# mcu.net
KiCad netlist of a schematic drawn in Altium Designer
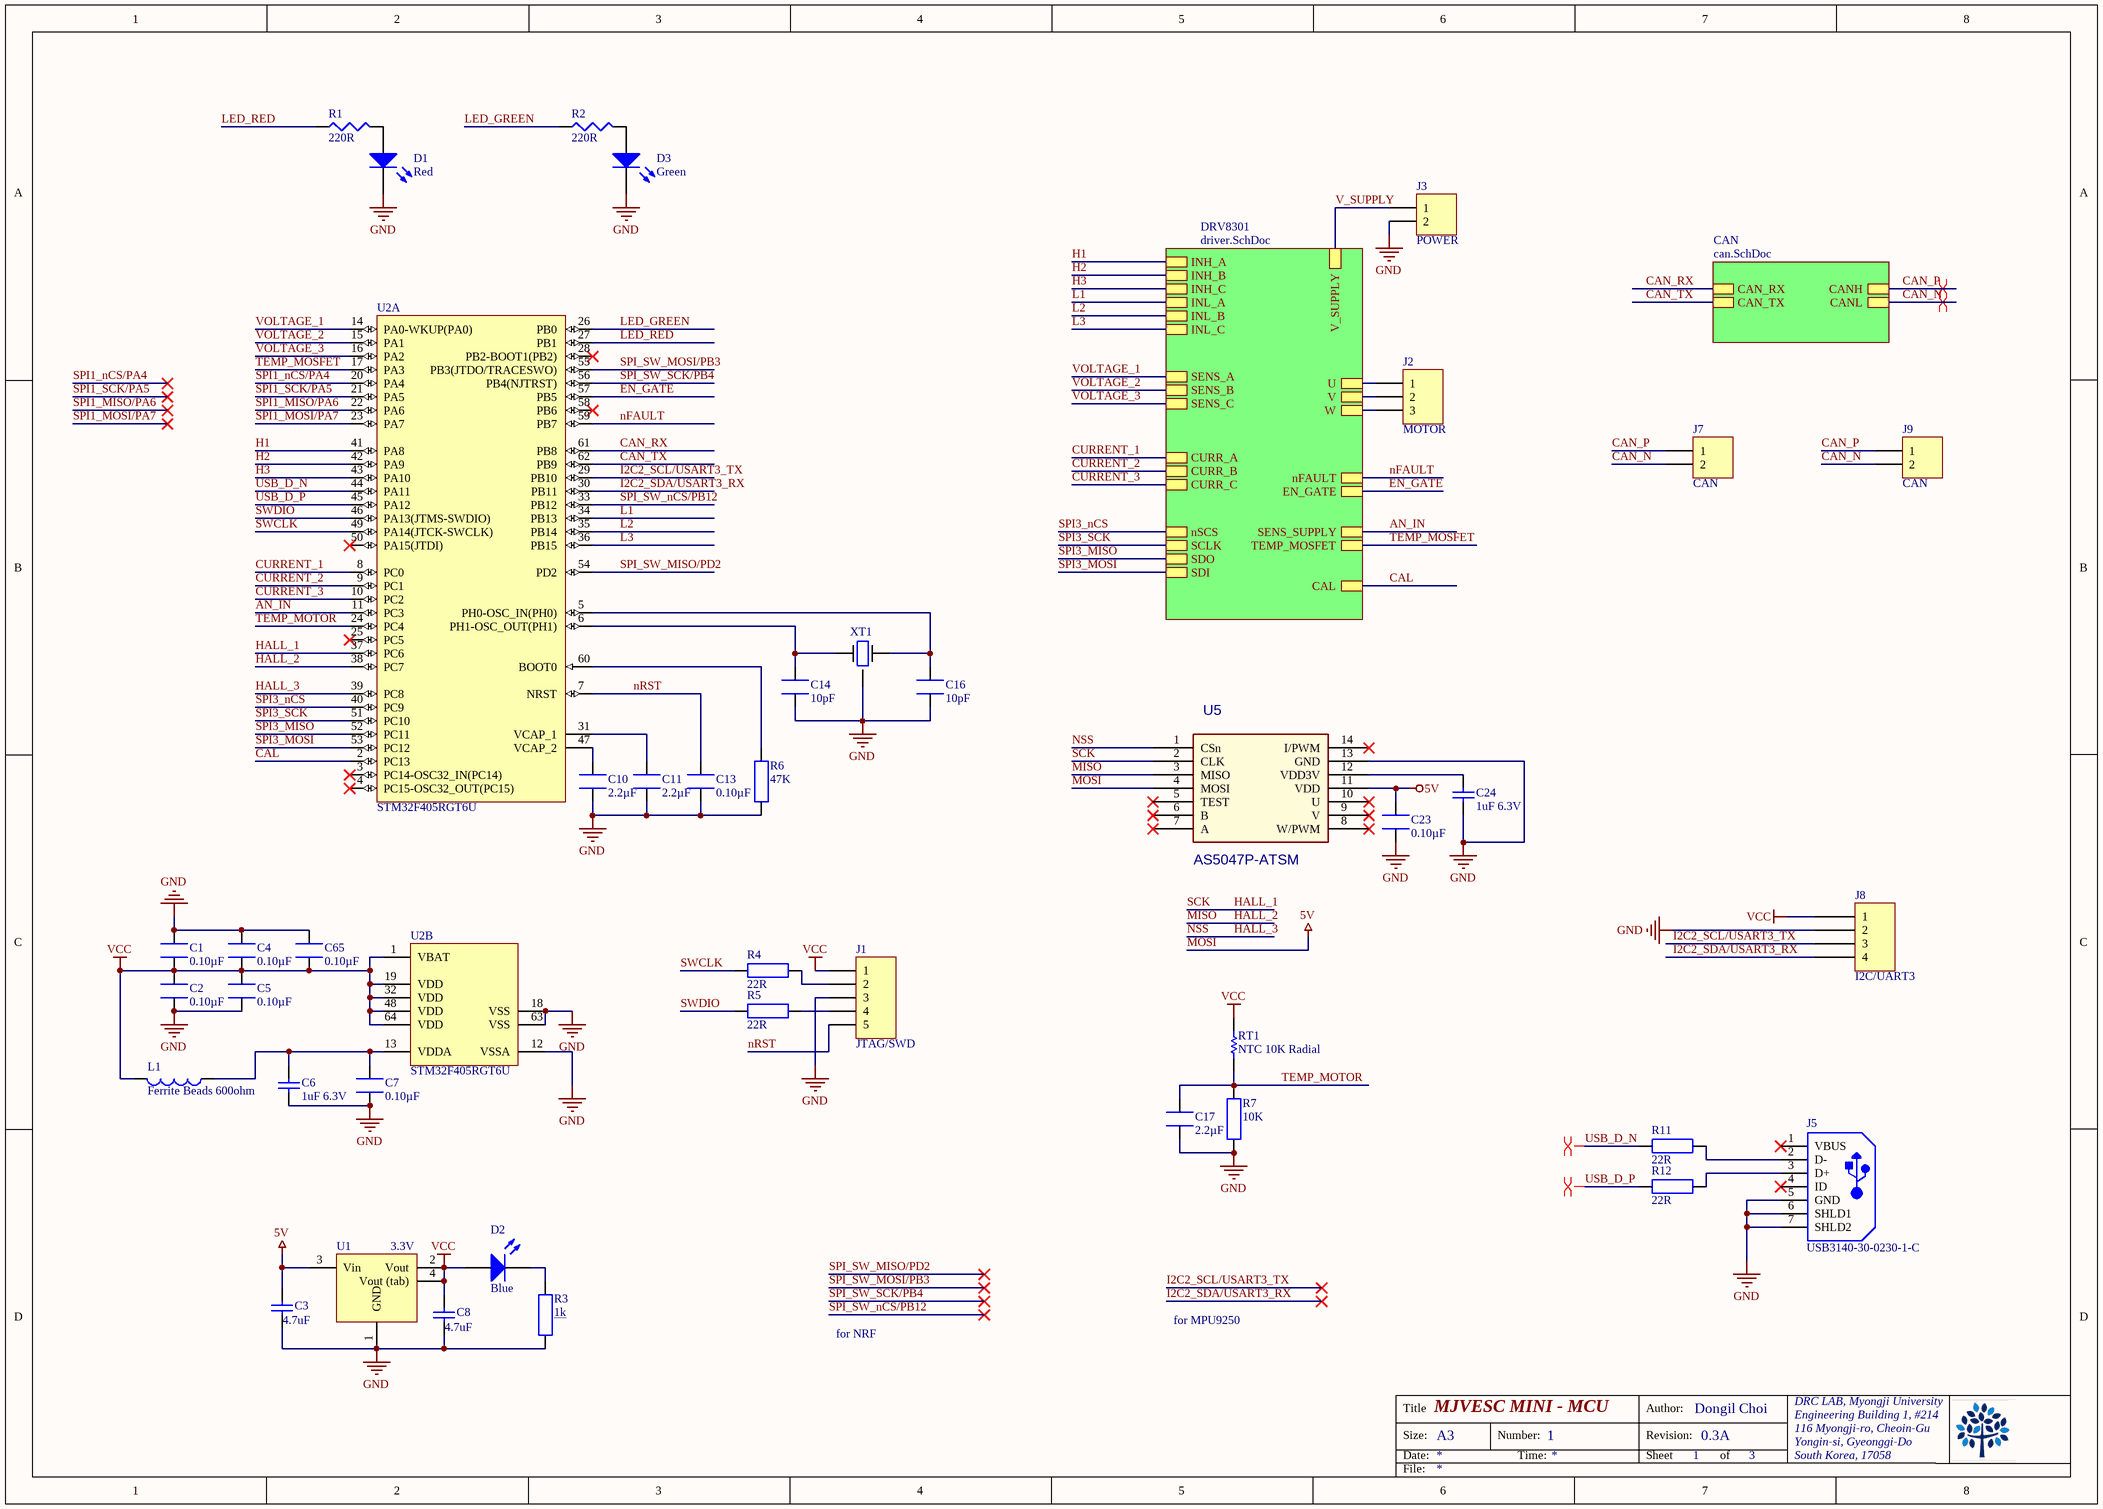
[diagram p0: mcu.SchDoc]

(export (version "E")
  (design (tool "Eeschema 10.0.6"))
  (components
    (comp (ref "C1")
      (value "0.10µF")
      (footprint "CAP 0603/1608")
      (description "CAP CER 0.1UF 25V X7R 0603")
      (fields
        (field (name "MANUFACTURER") "Murata Electronics North America")
        (field (name "MANUFACTURER PART NUMBER") "GRM188R71E104KA01D")
      )
      (libsource (lib "CustomComponents") (part "GRM188R71E104KA01D"))
    )
    (comp (ref "C2")
      (value "0.10µF")
      (footprint "CAP 0603/1608")
      (description "CAP CER 0.1UF 25V X7R 0603")
      (fields
        (field (name "MANUFACTURER") "Murata Electronics North America")
        (field (name "MANUFACTURER PART NUMBER") "GRM188R71E104KA01D")
      )
      (libsource (lib "CustomComponents") (part "GRM188R71E104KA01D"))
    )
    (comp (ref "C3")
      (value "4.7uF")
      (footprint "CAPC0805(2012)145_N")
      (description "CAP 4.7uF 35V ±10% 0805 (2012 Metric) Thickness 1.45mm SMD")
      (fields (field (name "TOLERANCE") "Â±10%") (field (name "PARTNUMBER") "GRM219R6YA475KA73D"))
      (libsource (lib "Altium Content Vault") (part "CAP"))
    )
    (comp (ref "C4")
      (value "0.10µF")
      (footprint "CAP 0603/1608")
      (description "CAP CER 0.1UF 25V X7R 0603")
      (fields
        (field (name "MANUFACTURER") "Murata Electronics North America")
        (field (name "MANUFACTURER PART NUMBER") "GRM188R71E104KA01D")
      )
      (libsource (lib "CustomComponents") (part "GRM188R71E104KA01D"))
    )
    (comp (ref "C5")
      (value "0.10µF")
      (footprint "CAP 0603/1608")
      (description "CAP CER 0.1UF 25V X7R 0603")
      (fields
        (field (name "MANUFACTURER") "Murata Electronics North America")
        (field (name "MANUFACTURER PART NUMBER") "GRM188R71E104KA01D")
      )
      (libsource (lib "CustomComponents") (part "GRM188R71E104KA01D"))
    )
    (comp (ref "C6")
      (value "1uF 6.3V")
      (footprint "CAPC0603(1608)100_N")
      (description "CAP 1uF 6.3V ±10% 0603 (1608 Metric) Thickness 1mm SMD")
      (fields (field (name "TOLERANCE") "Â±10%") (field (name "PARTNUMBER") "CC0603KRX7R5BB105"))
      (libsource (lib "Altium Content Vault") (part "CAP"))
    )
    (comp (ref "C7")
      (value "0.10µF")
      (footprint "CAP 0603/1608")
      (description "CAP CER 0.1UF 25V X7R 0603")
      (fields
        (field (name "MANUFACTURER") "Murata Electronics North America")
        (field (name "MANUFACTURER PART NUMBER") "GRM188R71E104KA01D")
      )
      (libsource (lib "CustomComponents") (part "GRM188R71E104KA01D"))
    )
    (comp (ref "C8")
      (value "4.7uF")
      (footprint "CAPC0805(2012)145_N")
      (description "CAP 4.7uF 35V ±10% 0805 (2012 Metric) Thickness 1.45mm SMD")
      (fields (field (name "TOLERANCE") "Â±10%") (field (name "PARTNUMBER") "GRM219R6YA475KA73D"))
      (libsource (lib "Altium Content Vault") (part "CAP"))
    )
    (comp (ref "C10")
      (value "2.2µF")
      (footprint "CAP 0603/1608")
      (description "CAP CER 2.2UF 16V X5R 0603")
      (fields
        (field (name "MANUFACTURER") "Murata Electronics North America")
        (field (name "MANUFACTURER PART NUMBER") "GRM188R61C225KE15D")
      )
      (libsource (lib "CustomComponents") (part "GRM188R61C225KE15D"))
    )
    (comp (ref "C11")
      (value "2.2µF")
      (footprint "CAP 0603/1608")
      (description "CAP CER 2.2UF 16V X5R 0603")
      (fields
        (field (name "MANUFACTURER") "Murata Electronics North America")
        (field (name "MANUFACTURER PART NUMBER") "GRM188R61C225KE15D")
      )
      (libsource (lib "CustomComponents") (part "GRM188R61C225KE15D"))
    )
    (comp (ref "C13")
      (value "0.10µF")
      (footprint "CAP 0603/1608")
      (description "CAP CER 0.1UF 25V X7R 0603")
      (fields
        (field (name "MANUFACTURER") "Murata Electronics North America")
        (field (name "MANUFACTURER PART NUMBER") "GRM188R71E104KA01D")
      )
      (libsource (lib "CustomComponents") (part "GRM188R71E104KA01D"))
    )
    (comp (ref "C14")
      (value "10pF")
      (footprint "CAP 0603/1608")
      (description "CAP CER 10PF 50V NP0 0603")
      (fields
        (field (name "MANUFACTURER") "Murata Electronics North America")
        (field (name "MANUFACTURER PART NUMBER") "GRM1885C1H100JA01D")
      )
      (libsource (lib "CustomComponents") (part "GRM1885C1H100JA01D"))
    )
    (comp (ref "C16")
      (value "10pF")
      (footprint "CAP 0603/1608")
      (description "CAP CER 10PF 50V NP0 0603")
      (fields
        (field (name "MANUFACTURER") "Murata Electronics North America")
        (field (name "MANUFACTURER PART NUMBER") "GRM1885C1H100JA01D")
      )
      (libsource (lib "CustomComponents") (part "GRM1885C1H100JA01D"))
    )
    (comp (ref "C17")
      (value "2.2µF")
      (footprint "CAP 0603/1608")
      (description "CAP CER 2.2UF 16V X5R 0603")
      (fields
        (field (name "MANUFACTURER") "Murata Electronics North America")
        (field (name "MANUFACTURER PART NUMBER") "GRM188R61C225KE15D")
      )
      (libsource (lib "CustomComponents") (part "GRM188R61C225KE15D"))
    )
    (comp (ref "C23")
      (value "0.10µF")
      (footprint "CAP 0603/1608")
      (description "CAP CER 0.1UF 25V X7R 0603")
      (fields
        (field (name "MANUFACTURER") "Murata Electronics North America")
        (field (name "MANUFACTURER PART NUMBER") "GRM188R71E104KA01D")
      )
      (libsource (lib "CustomComponents") (part "GRM188R71E104KA01D"))
    )
    (comp (ref "C24")
      (value "1uF 6.3V")
      (footprint "CAPC0603(1608)100_N")
      (description "CAP 1uF 6.3V ±10% 0603 (1608 Metric) Thickness 1mm SMD")
      (fields (field (name "TOLERANCE") "Â±10%") (field (name "PARTNUMBER") "CC0603KRX7R5BB105"))
      (libsource (lib "Altium Content Vault") (part "CAP"))
    )
    (comp (ref "C65")
      (value "0.10µF")
      (footprint "CAP 0603/1608")
      (description "CAP CER 0.1UF 25V X7R 0603")
      (fields
        (field (name "MANUFACTURER") "Murata Electronics North America")
        (field (name "MANUFACTURER PART NUMBER") "GRM188R71E104KA01D")
      )
      (libsource (lib "CustomComponents") (part "GRM188R71E104KA01D"))
    )
    (comp (ref "D1")
      (value "Red")
      (footprint "LED 0603/1608 RED")
      (description "Typical INFRARED GaAs LED")
      (fields (field (name "PARTNUMBER") "LTST-C191KRKT") (field (name "PUBLISHER") "Altium Limited"))
      (libsource (lib "Miscellaneous Devices") (part "LED0"))
    )
    (comp (ref "D2")
      (value "Blue")
      (footprint "LED 0603/1608 BLUE")
      (description "Typical INFRARED GaAs LED")
      (fields (field (name "PARTNUMBER") "LTST-C191TBKT") (field (name "PUBLISHER") "Altium Limited"))
      (libsource (lib "Miscellaneous Devices") (part "LED0"))
    )
    (comp (ref "D3")
      (value "Green")
      (footprint "LED 0603/1608 GREEN")
      (description "Typical INFRARED GaAs LED")
      (fields (field (name "PARTNUMBER") "LTST-C191KGKT") (field (name "PUBLISHER") "Altium Limited"))
      (libsource (lib "Miscellaneous Devices") (part "LED0"))
    )
    (comp (ref "J1")
      (value "JTAG/SWD")
      (footprint "JST BM05B-GHS-TBT")
      (description "JST GH Connector, 5Pin, Vertical")
      (fields (field (name "PARTNUMBER") "BM05B-GHS-TBT") (field (name "PUBLISHER") "Altium Limited"))
      (libsource (lib "Altium_CDI_Library_Combined") (part "JST BM05B-GHS-TBT"))
    )
    (comp (ref "J2")
      (value "MOTOR")
      (footprint "MR30PW - MIRROR")
      (description "AMASS, MR30,  on PCBs, 30A 500V, UL94V, -20...120°C")
      (fields (field (name "PUBLISHER") "Altium Limited"))
      (libsource (lib "Altium_CDI_Library_Combined") (part "MR30PW-M"))
    )
    (comp (ref "J3")
      (value "POWER")
      (footprint "XT30PW - MIRROR")
      (description "AMASS, XT30,  on PCBs, 30A 500V, UL94V, -20...120°C")
      (fields (field (name "PUBLISHER") "Altium Limited"))
      (libsource (lib "Altium_CDI_Library_Combined") (part "XT30PW-M"))
    )
    (comp (ref "J5")
      (value "USB3140-30-0230-1-C")
      (footprint "GCT-USB3140_V")
      (fields
        (field (name "PARTNUMBER") "USB3140")
        (field (name "MANUFACTURER") "Global Connector Technology")
      )
      (libsource (lib "Altium Content Vault") (part "USB-5-2SHLD"))
    )
    (comp (ref "J7")
      (value "CAN")
      (footprint "JST SM02B-GHS-TB")
      (description "JST GH Connector, 2Pin")
      (fields (field (name "PARTNUMBER") "SM02B-GHS-TB(LF)(SN)") (field (name "PUBLISHER") "Altium Limited"))
      (libsource (lib "Altium_CDI_Library_Combined") (part "JST SM02B-GH"))
    )
    (comp (ref "J8")
      (value "I2C/UART3")
      (footprint "JST BM04B-GHS-TBT")
      (description "JST GH Connector, 4Pin")
      (fields (field (name "PARTNUMBER") "BM04B-GHS-TB(LF)(SN)"))
      (libsource (lib "Altium_CDI_Library_Combined") (part "JST BM04B-GH"))
    )
    (comp (ref "J9")
      (value "CAN")
      (footprint "JST SM02B-GHS-TB")
      (description "JST GH Connector, 2Pin")
      (fields (field (name "PARTNUMBER") "SM02B-GHS-TB(LF)(SN)") (field (name "PUBLISHER") "Altium Limited"))
      (libsource (lib "Altium_CDI_Library_Combined") (part "JST SM02B-GH"))
    )
    (comp (ref "L1")
      (value "Ferrite Beads 600ohm")
      (footprint "FER 0603/1608")
      (description "Ferrite Beads 600MHz 0.015Ohm 25% 1608 AEC-Q200")
      (fields (field (name "PARTNUMBER") "KPZ1608SHR601ATD25") (field (name "PUBLISHER") "Altium Limited"))
      (libsource (lib "Miscellaneous Devices") (part "Inductor"))
    )
    (comp (ref "R1")
      (value "220R")
      (footprint "RES 0603/1608")
      (description "RES SMD 220R OHM 1% 1/10W 0603")
      (fields (field (name "PARTNUMBER") "RC0603FR-10220RL") (field (name "PUBLISHER") "Altium Limited"))
      (libsource (lib "Miscellaneous Devices") (part "Res3"))
    )
    (comp (ref "R2")
      (value "220R")
      (footprint "RES 0603/1608")
      (description "RES SMD 220R OHM 1% 1/10W 0603")
      (fields (field (name "PARTNUMBER") "RC0603FR-10220RL") (field (name "PUBLISHER") "Altium Limited"))
      (libsource (lib "Miscellaneous Devices") (part "Res3"))
    )
    (comp (ref "R3")
      (value "1k")
      (footprint "RES 0603/1608")
      (description "RES SMD 1K OHM 1% 1/10W 0603")
      (fields (field (name "MANUFACTURER") "Yageo") (field (name "TOLERANCE") "±1%"))
      (libsource (lib "CustomComponents") (part "RC0603FR-071KL"))
    )
    (comp (ref "R4")
      (value "22R")
      (footprint "RES 0603/1608")
      (description "RES SMD 22 OHM 1% 1/10W 0603")
      (fields
        (field (name "MANUFACTURER") "Yageo")
        (field (name "MANUFACTURER PART NUMBER") "RC0603FR-0722RL")
      )
      (libsource (lib "CustomComponents") (part "RC0603FR-0722RL"))
    )
    (comp (ref "R5")
      (value "22R")
      (footprint "RES 0603/1608")
      (description "RES SMD 22 OHM 1% 1/10W 0603")
      (fields
        (field (name "MANUFACTURER") "Yageo")
        (field (name "MANUFACTURER PART NUMBER") "RC0603FR-0722RL")
      )
      (libsource (lib "CustomComponents") (part "RC0603FR-0722RL"))
    )
    (comp (ref "R6")
      (value "47K")
      (footprint "RES 0603/1608")
      (description "RES SMD 47K OHM 1% 1/10W 0603")
      (fields
        (field (name "MANUFACTURER") "Yageo")
        (field (name "MANUFACTURER PART NUMBER") "RC0603FR-0747KL")
      )
      (libsource (lib "CustomComponents") (part "RC0603FR-0747KL"))
    )
    (comp (ref "R7")
      (value "10K")
      (footprint "RES 0603/1608")
      (description "RES SMD 10K OHM 1% 1/10W 0603")
      (fields
        (field (name "MANUFACTURER") "Yageo")
        (field (name "MANUFACTURER PART NUMBER") "RC0603FR-0710KL")
      )
      (libsource (lib "CustomComponents") (part "RC0603FR-0710KL"))
    )
    (comp (ref "R11")
      (value "22R")
      (footprint "RES 0603/1608")
      (description "RES SMD 22 OHM 1% 1/10W 0603")
      (fields
        (field (name "MANUFACTURER") "Yageo")
        (field (name "MANUFACTURER PART NUMBER") "RC0603FR-0722RL")
      )
      (libsource (lib "CustomComponents") (part "RC0603FR-0722RL"))
    )
    (comp (ref "R12")
      (value "22R")
      (footprint "RES 0603/1608")
      (description "RES SMD 22 OHM 1% 1/10W 0603")
      (fields
        (field (name "MANUFACTURER") "Yageo")
        (field (name "MANUFACTURER PART NUMBER") "RC0603FR-0722RL")
      )
      (libsource (lib "CustomComponents") (part "RC0603FR-0722RL"))
    )
    (comp (ref "RT1")
      (value "NTC 10K Radial")
      (footprint "SEMI-103AT-2_V")
      (description "NTC Thermistors 10Kohms 5% Radial\r\nNTCLE100E3103JT2 (Vishay - cheap)")
      (fields (field (name "MANUFACTURER") "Semitec") (field (name "TOLERANCE") "1%"))
      (libsource (lib "Altium Content Vault") (part "RES-THERMAL-2"))
    )
    (comp (ref "U1")
      (value "3.3V")
      (footprint "SOT-223-2")
      (description "IC REG LDO 3.3V 1A SOT223")
      (fields
        (field (name "MANUFACTURER") "Diodes Incorporated")
        (field (name "PARTNUMBER") "AZ1117EH-3.3TRG1")
      )
      (libsource (lib "CustomComponents") (part "AZ1117EH-3.3TRG1"))
    )
    (comp (ref "U2")
      (value "STM32F405RGT6U")
      (footprint "STM-LQFP64_V")
      (fields (field (name "MANUFACTURER") "STMicroelectronics"))
      (libsource (lib "Altium_CDI_Library_Combined") (part "STM32F405RGT6"))
    )
    (comp (ref "U5")
      (value "AS5047P-ATSM")
      (footprint "AMS-TSSOP-14-5000X4400DE_M")
      (description "AS5147-HTSM")
      (libsource (lib "Altium_CDI_Library_Combined") (part "AS5147"))
    )
    (comp (ref "XT1")
      (value "8 MHz")
      (footprint "DFN220P320X110-4N")
      (description "Crystal 8MHz ±10ppm 10pF 200 Ohm -10°C ~ 60°C Surface Mount 4-SMD, No Lead (DFN, LCC)")
      (fields (field (name "PARTNUMBER") "ABM3B-8.000MHZ-10-1UT"))
      (libsource (lib "CustomComponents") (part "ABM3B-8.000MHZ-10-1-U-T"))
    )
  )
  (nets
    (net (code "1") (name "/AN_IN") (class "Default")
      (node (ref "U2") (pin "11") (pinfunction "PC3_11") (pintype "bidirectional"))
    )
    (net (code "2") (name "/CAL") (class "Default")
      (node (ref "U2") (pin "2") (pinfunction "PC13_2") (pintype "bidirectional"))
    )
    (net (code "3") (name "/CAN_N") (class "Default")
      (node (ref "J7") (pin "2") (pinfunction "2_2") (pintype "passive"))
      (node (ref "J9") (pin "2") (pinfunction "2_2") (pintype "passive"))
    )
    (net (code "4") (name "/CAN_P") (class "Default")
      (node (ref "J7") (pin "1") (pinfunction "1_1") (pintype "passive"))
      (node (ref "J9") (pin "1") (pinfunction "1_1") (pintype "passive"))
    )
    (net (code "5") (name "/CAN_RX") (class "Default")
      (node (ref "U2") (pin "61") (pinfunction "PB8_61") (pintype "bidirectional"))
    )
    (net (code "6") (name "/CAN_TX") (class "Default")
      (node (ref "U2") (pin "62") (pinfunction "PB9_62") (pintype "bidirectional"))
    )
    (net (code "7") (name "/CURRENT_1") (class "Default")
      (node (ref "U2") (pin "8") (pinfunction "PC0_8") (pintype "bidirectional"))
    )
    (net (code "8") (name "/CURRENT_2") (class "Default")
      (node (ref "U2") (pin "9") (pinfunction "PC1_9") (pintype "bidirectional"))
    )
    (net (code "9") (name "/CURRENT_3") (class "Default")
      (node (ref "U2") (pin "10") (pinfunction "PC2_10") (pintype "bidirectional"))
    )
    (net (code "10") (name "/EN_GATE") (class "Default")
      (node (ref "U2") (pin "57") (pinfunction "PB5_57") (pintype "bidirectional"))
    )
    (net (code "11") (name "/H1") (class "Default")
      (node (ref "U2") (pin "41") (pinfunction "PA8_41") (pintype "bidirectional"))
    )
    (net (code "12") (name "/H2") (class "Default")
      (node (ref "U2") (pin "42") (pinfunction "PA9_42") (pintype "bidirectional"))
    )
    (net (code "13") (name "/H3") (class "Default")
      (node (ref "U2") (pin "43") (pinfunction "PA10_43") (pintype "bidirectional"))
    )
    (net (code "14") (name "/HALL_1") (class "Default")
      (node (ref "U2") (pin "37") (pinfunction "PC6_37") (pintype "bidirectional"))
      (node (ref "U5") (pin "2") (pinfunction "CLK_2") (pintype "passive"))
    )
    (net (code "15") (name "/HALL_2") (class "Default")
      (node (ref "U2") (pin "38") (pinfunction "PC7_38") (pintype "bidirectional"))
      (node (ref "U5") (pin "3") (pinfunction "MISO_3") (pintype "passive"))
    )
    (net (code "16") (name "/HALL_3") (class "Default")
      (node (ref "U2") (pin "39") (pinfunction "PC8_39") (pintype "bidirectional"))
      (node (ref "U5") (pin "1") (pinfunction "CSn_1") (pintype "passive"))
    )
    (net (code "17") (name "/I2C2_SCL{slash}USART3_TX") (class "Default")
      (node (ref "J8") (pin "3") (pinfunction "3_3") (pintype "passive"))
      (node (ref "U2") (pin "29") (pinfunction "PB10_29") (pintype "bidirectional"))
    )
    (net (code "18") (name "/I2C2_SDA{slash}USART3_RX") (class "Default")
      (node (ref "J8") (pin "4") (pinfunction "4_4") (pintype "passive"))
      (node (ref "U2") (pin "30") (pinfunction "PB11_30") (pintype "bidirectional"))
    )
    (net (code "19") (name "/L1") (class "Default")
      (node (ref "U2") (pin "34") (pinfunction "PB13_34") (pintype "bidirectional"))
    )
    (net (code "20") (name "/L2") (class "Default")
      (node (ref "U2") (pin "35") (pinfunction "PB14_35") (pintype "bidirectional"))
    )
    (net (code "21") (name "/L3") (class "Default")
      (node (ref "U2") (pin "36") (pinfunction "PB15_36") (pintype "bidirectional"))
    )
    (net (code "22") (name "/LED_GREEN") (class "Default")
      (node (ref "R2") (pin "1") (pinfunction "1_1") (pintype "passive"))
      (node (ref "U2") (pin "26") (pinfunction "PB0_26") (pintype "bidirectional"))
    )
    (net (code "23") (name "/LED_RED") (class "Default")
      (node (ref "R1") (pin "1") (pinfunction "1_1") (pintype "passive"))
      (node (ref "U2") (pin "27") (pinfunction "PB1_27") (pintype "bidirectional"))
    )
    (net (code "24") (name "/SPI1_MISO{slash}PA6") (class "Default")
      (node (ref "U2") (pin "22") (pinfunction "PA6_22") (pintype "bidirectional+no_connect"))
    )
    (net (code "25") (name "/SPI1_MOSI{slash}PA7") (class "Default")
      (node (ref "U2") (pin "23") (pinfunction "PA7_23") (pintype "bidirectional+no_connect"))
    )
    (net (code "26") (name "/SPI1_SCK{slash}PA5") (class "Default")
      (node (ref "U2") (pin "21") (pinfunction "PA5_21") (pintype "bidirectional+no_connect"))
    )
    (net (code "27") (name "/SPI1_nCS{slash}PA4") (class "Default")
      (node (ref "U2") (pin "20") (pinfunction "PA4_20") (pintype "bidirectional+no_connect"))
    )
    (net (code "28") (name "/SPI3_MISO") (class "Default")
      (node (ref "U2") (pin "52") (pinfunction "PC11_52") (pintype "bidirectional"))
    )
    (net (code "29") (name "/SPI3_MOSI") (class "Default")
      (node (ref "U2") (pin "53") (pinfunction "PC12_53") (pintype "bidirectional"))
    )
    (net (code "30") (name "/SPI3_SCK") (class "Default")
      (node (ref "U2") (pin "51") (pinfunction "PC10_51") (pintype "bidirectional"))
    )
    (net (code "31") (name "/SPI3_nCS") (class "Default")
      (node (ref "U2") (pin "40") (pinfunction "PC9_40") (pintype "bidirectional"))
    )
    (net (code "32") (name "/SPI_SW_MISO{slash}PD2") (class "Default")
      (node (ref "U2") (pin "54") (pinfunction "PD2_54") (pintype "bidirectional+no_connect"))
    )
    (net (code "33") (name "/SPI_SW_MOSI{slash}PB3") (class "Default")
      (node (ref "U2") (pin "55") (pinfunction "PB3(JTDO/TRACESWO)_55") (pintype "bidirectional+no_connect"))
    )
    (net (code "34") (name "/SPI_SW_SCK{slash}PB4") (class "Default")
      (node (ref "U2") (pin "56") (pinfunction "PB4(NJTRST)_56") (pintype "bidirectional+no_connect"))
    )
    (net (code "35") (name "/SPI_SW_nCS{slash}PB12") (class "Default")
      (node (ref "U2") (pin "33") (pinfunction "PB12_33") (pintype "bidirectional+no_connect"))
    )
    (net (code "36") (name "/SWCLK") (class "Default")
      (node (ref "R4") (pin "2") (pinfunction "0_2") (pintype "passive"))
      (node (ref "U2") (pin "49") (pinfunction "PA14(JTCK-SWCLK)_49") (pintype "bidirectional"))
    )
    (net (code "37") (name "/SWDIO") (class "Default")
      (node (ref "R5") (pin "2") (pinfunction "0_2") (pintype "passive"))
      (node (ref "U2") (pin "46") (pinfunction "PA13(JTMS-SWDIO)_46") (pintype "bidirectional"))
    )
    (net (code "38") (name "/TEMP_MOSFET") (class "Default")
      (node (ref "U2") (pin "17") (pinfunction "PA3_17") (pintype "bidirectional"))
    )
    (net (code "39") (name "/TEMP_MOTOR") (class "Default")
      (node (ref "C17") (pin "2") (pinfunction "2_2") (pintype "passive"))
      (node (ref "R7") (pin "1") (pinfunction "0_1") (pintype "passive"))
      (node (ref "RT1") (pin "1") (pinfunction "1_1") (pintype "passive"))
      (node (ref "U2") (pin "24") (pinfunction "PC4_24") (pintype "bidirectional"))
    )
    (net (code "40") (name "/U") (class "Default")
      (node (ref "J2") (pin "1") (pinfunction "1_1") (pintype "passive"))
    )
    (net (code "41") (name "/USB_D_N") (class "Default")
      (node (ref "R11") (pin "1") (pinfunction "0_1") (pintype "passive"))
      (node (ref "U2") (pin "44") (pinfunction "PA11_44") (pintype "bidirectional"))
    )
    (net (code "42") (name "/USB_D_P") (class "Default")
      (node (ref "R12") (pin "1") (pinfunction "0_1") (pintype "passive"))
      (node (ref "U2") (pin "45") (pinfunction "PA12_45") (pintype "bidirectional"))
    )
    (net (code "43") (name "/V") (class "Default")
      (node (ref "J2") (pin "2") (pinfunction "2_2") (pintype "passive"))
    )
    (net (code "44") (name "/VOLTAGE_1") (class "Default")
      (node (ref "U2") (pin "14") (pinfunction "PA0-WKUP(PA0)_14") (pintype "bidirectional"))
    )
    (net (code "45") (name "/VOLTAGE_2") (class "Default")
      (node (ref "U2") (pin "15") (pinfunction "PA1_15") (pintype "bidirectional"))
    )
    (net (code "46") (name "/VOLTAGE_3") (class "Default")
      (node (ref "U2") (pin "16") (pinfunction "PA2_16") (pintype "bidirectional"))
    )
    (net (code "47") (name "/V_SUPPLY") (class "Default")
      (node (ref "J3") (pin "1") (pinfunction "1_1") (pintype "passive"))
    )
    (net (code "48") (name "/W") (class "Default")
      (node (ref "J2") (pin "3") (pinfunction "3_3") (pintype "passive"))
    )
    (net (code "49") (name "/nFAULT") (class "Default")
      (node (ref "U2") (pin "59") (pinfunction "PB7_59") (pintype "bidirectional"))
    )
    (net (code "50") (name "/nRST") (class "Default")
      (node (ref "C13") (pin "2") (pinfunction "2_2") (pintype "passive"))
      (node (ref "J1") (pin "5") (pinfunction "5_5") (pintype "passive"))
      (node (ref "U2") (pin "7") (pinfunction "NRST_7") (pintype "bidirectional"))
    )
    (net (code "51") (name "5V") (class "Default")
      (node (ref "C23") (pin "2") (pinfunction "2_2") (pintype "passive"))
      (node (ref "C3") (pin "2") (pinfunction "2_2") (pintype "passive"))
      (node (ref "U1") (pin "3") (pinfunction "Vin_3") (pintype "passive"))
      (node (ref "U5") (pin "11") (pinfunction "VDD_11") (pintype "passive"))
      (node (ref "U5") (pin "4") (pinfunction "MOSI_4") (pintype "passive"))
    )
    (net (code "52") (name "GND") (class "Default")
      (node (ref "C1") (pin "1") (pinfunction "1_1") (pintype "passive"))
      (node (ref "C10") (pin "1") (pinfunction "1_1") (pintype "passive"))
      (node (ref "C11") (pin "1") (pinfunction "1_1") (pintype "passive"))
      (node (ref "C13") (pin "1") (pinfunction "1_1") (pintype "passive"))
      (node (ref "C14") (pin "2") (pinfunction "2_2") (pintype "passive"))
      (node (ref "C16") (pin "2") (pinfunction "2_2") (pintype "passive"))
      (node (ref "C17") (pin "1") (pinfunction "1_1") (pintype "passive"))
      (node (ref "C2") (pin "2") (pinfunction "2_2") (pintype "passive"))
      (node (ref "C23") (pin "1") (pinfunction "1_1") (pintype "passive"))
      (node (ref "C24") (pin "2") (pinfunction "2_2") (pintype "passive"))
      (node (ref "C3") (pin "1") (pinfunction "1_1") (pintype "passive"))
      (node (ref "C4") (pin "1") (pinfunction "1_1") (pintype "passive"))
      (node (ref "C5") (pin "2") (pinfunction "2_2") (pintype "passive"))
      (node (ref "C6") (pin "2") (pinfunction "2_2") (pintype "passive"))
      (node (ref "C65") (pin "1") (pinfunction "1_1") (pintype "passive"))
      (node (ref "C7") (pin "2") (pinfunction "2_2") (pintype "passive"))
      (node (ref "C8") (pin "1") (pinfunction "1_1") (pintype "passive"))
      (node (ref "D1") (pin "2") (pinfunction "K_2") (pintype "passive"))
      (node (ref "D3") (pin "2") (pinfunction "K_2") (pintype "passive"))
      (node (ref "J1") (pin "3") (pinfunction "3_3") (pintype "passive"))
      (node (ref "J3") (pin "2") (pinfunction "2_2") (pintype "passive"))
      (node (ref "J5") (pin "5") (pinfunction "GND_5") (pintype "passive"))
      (node (ref "J5") (pin "6") (pinfunction "SHLD1_6") (pintype "passive"))
      (node (ref "J5") (pin "7") (pinfunction "SHLD2_7") (pintype "passive"))
      (node (ref "J8") (pin "2") (pinfunction "2_2") (pintype "passive"))
      (node (ref "R3") (pin "2") (pinfunction "0_2") (pintype "passive"))
      (node (ref "R6") (pin "1") (pinfunction "0_1") (pintype "passive"))
      (node (ref "R7") (pin "2") (pinfunction "0_2") (pintype "passive"))
      (node (ref "U1") (pin "1") (pinfunction "GND_1") (pintype "passive"))
      (node (ref "U2") (pin "12") (pinfunction "VSSA_12") (pintype "power_in"))
      (node (ref "U2") (pin "18") (pinfunction "VSS_18") (pintype "power_in"))
      (node (ref "U2") (pin "63") (pinfunction "VSS_63") (pintype "power_in"))
      (node (ref "U5") (pin "13") (pinfunction "GND_13") (pintype "passive"))
      (node (ref "XT1") (pin "G") (pintype "passive"))
    )
    (net (code "53") (name "Net-(D1-A)") (class "Default")
      (node (ref "D1") (pin "1") (pinfunction "A_1") (pintype "passive"))
      (node (ref "R1") (pin "2") (pinfunction "2_2") (pintype "passive"))
    )
    (net (code "54") (name "Net-(D2-K)") (class "Default")
      (node (ref "D2") (pin "2") (pinfunction "K_2") (pintype "passive"))
      (node (ref "R3") (pin "1") (pinfunction "0_1") (pintype "passive"))
    )
    (net (code "55") (name "Net-(D3-A)") (class "Default")
      (node (ref "D3") (pin "1") (pinfunction "A_1") (pintype "passive"))
      (node (ref "R2") (pin "2") (pinfunction "2_2") (pintype "passive"))
    )
    (net (code "56") (name "Net-(J1-Pad2)") (class "Default")
      (node (ref "J1") (pin "2") (pinfunction "2_2") (pintype "passive"))
      (node (ref "R4") (pin "1") (pinfunction "0_1") (pintype "passive"))
    )
    (net (code "57") (name "Net-(J1-Pad4)") (class "Default")
      (node (ref "J1") (pin "4") (pinfunction "4_4") (pintype "passive"))
      (node (ref "R5") (pin "1") (pinfunction "0_1") (pintype "passive"))
    )
    (net (code "58") (name "Net-(J5-D+)") (class "Default")
      (node (ref "J5") (pin "3") (pinfunction "D+_3") (pintype "passive"))
      (node (ref "R12") (pin "2") (pinfunction "0_2") (pintype "passive"))
    )
    (net (code "59") (name "Net-(J5-D-)") (class "Default")
      (node (ref "J5") (pin "2") (pinfunction "D-_2") (pintype "passive"))
      (node (ref "R11") (pin "2") (pinfunction "0_2") (pintype "passive"))
    )
    (net (code "60") (name "Net-(U2A-BOOT0)") (class "Default")
      (node (ref "R6") (pin "2") (pinfunction "0_2") (pintype "passive"))
      (node (ref "U2") (pin "60") (pinfunction "BOOT0_60") (pintype "input"))
    )
    (net (code "61") (name "Net-(U2A-PH0-OSC_IN(PH0))") (class "Default")
      (node (ref "C16") (pin "1") (pinfunction "1_1") (pintype "passive"))
      (node (ref "U2") (pin "5") (pinfunction "PH0-OSC_IN(PH0)_5") (pintype "bidirectional"))
      (node (ref "XT1") (pin "3") (pintype "passive"))
    )
    (net (code "62") (name "Net-(U2A-PH1-OSC_OUT(PH1))") (class "Default")
      (node (ref "C14") (pin "1") (pinfunction "1_1") (pintype "passive"))
      (node (ref "U2") (pin "6") (pinfunction "PH1-OSC_OUT(PH1)_6") (pintype "bidirectional"))
      (node (ref "XT1") (pin "1") (pintype "passive"))
    )
    (net (code "63") (name "Net-(U2A-VCAP_1)") (class "Default")
      (node (ref "C11") (pin "2") (pinfunction "2_2") (pintype "passive"))
      (node (ref "U2") (pin "31") (pinfunction "VCAP_1_31") (pintype "power_in"))
    )
    (net (code "64") (name "Net-(U2A-VCAP_2)") (class "Default")
      (node (ref "C10") (pin "2") (pinfunction "2_2") (pintype "passive"))
      (node (ref "U2") (pin "47") (pinfunction "VCAP_2_47") (pintype "power_in"))
    )
    (net (code "65") (name "Net-(U2B-VDDA)") (class "Default")
      (node (ref "C6") (pin "1") (pinfunction "1_1") (pintype "passive"))
      (node (ref "C7") (pin "1") (pinfunction "1_1") (pintype "passive"))
      (node (ref "L1") (pin "1") (pinfunction "1_1") (pintype "passive"))
      (node (ref "U2") (pin "13") (pinfunction "VDDA_13") (pintype "power_in"))
    )
    (net (code "66") (name "Net-(U5-VDD3V)") (class "Default")
      (node (ref "C24") (pin "1") (pinfunction "1_1") (pintype "passive"))
      (node (ref "U5") (pin "12") (pinfunction "VDD3V_12") (pintype "passive"))
    )
    (net (code "67") (name "VCC") (class "Default")
      (node (ref "C1") (pin "2") (pinfunction "2_2") (pintype "passive"))
      (node (ref "C2") (pin "1") (pinfunction "1_1") (pintype "passive"))
      (node (ref "C4") (pin "2") (pinfunction "2_2") (pintype "passive"))
      (node (ref "C5") (pin "1") (pinfunction "1_1") (pintype "passive"))
      (node (ref "C65") (pin "2") (pinfunction "2_2") (pintype "passive"))
      (node (ref "C8") (pin "2") (pinfunction "2_2") (pintype "passive"))
      (node (ref "D2") (pin "1") (pinfunction "A_1") (pintype "passive"))
      (node (ref "J1") (pin "1") (pinfunction "1_1") (pintype "passive"))
      (node (ref "J8") (pin "1") (pinfunction "1_1") (pintype "passive"))
      (node (ref "L1") (pin "2") (pinfunction "2_2") (pintype "passive"))
      (node (ref "RT1") (pin "2") (pinfunction "2_2") (pintype "passive"))
      (node (ref "U1") (pin "2") (pinfunction "Vout_2") (pintype "passive"))
      (node (ref "U1") (pin "4") (pinfunction "Vout_(tab)_4") (pintype "passive"))
      (node (ref "U2") (pin "1") (pinfunction "VBAT_1") (pintype "power_in"))
      (node (ref "U2") (pin "19") (pinfunction "VDD_19") (pintype "power_in"))
      (node (ref "U2") (pin "32") (pinfunction "VDD_32") (pintype "power_in"))
      (node (ref "U2") (pin "48") (pinfunction "VDD_48") (pintype "power_in"))
      (node (ref "U2") (pin "64") (pinfunction "VDD_64") (pintype "power_in"))
    )
    (net (code "68") (name "unconnected-(J5-ID-Pad4)") (class "Default")
      (node (ref "J5") (pin "4") (pinfunction "ID_4") (pintype "passive+no_connect"))
    )
    (net (code "69") (name "unconnected-(J5-VBUS-Pad1)") (class "Default")
      (node (ref "J5") (pin "1") (pinfunction "VBUS_1") (pintype "passive+no_connect"))
    )
    (net (code "70") (name "unconnected-(U2A-PA15(JTDI)-Pad50)") (class "Default")
      (node (ref "U2") (pin "50") (pinfunction "PA15(JTDI)_50") (pintype "bidirectional+no_connect"))
    )
    (net (code "71") (name "unconnected-(U2A-PB2-BOOT1(PB2)-Pad28)") (class "Default")
      (node (ref "U2") (pin "28") (pinfunction "PB2-BOOT1(PB2)_28") (pintype "bidirectional+no_connect"))
    )
    (net (code "72") (name "unconnected-(U2A-PB6-Pad58)") (class "Default")
      (node (ref "U2") (pin "58") (pinfunction "PB6_58") (pintype "bidirectional+no_connect"))
    )
    (net (code "73") (name "unconnected-(U2A-PC5-Pad25)") (class "Default")
      (node (ref "U2") (pin "25") (pinfunction "PC5_25") (pintype "bidirectional+no_connect"))
    )
    (net (code "74") (name "unconnected-(U2A-PC14-OSC32_IN(PC14)-Pad3)") (class "Default")
      (node (ref "U2") (pin "3") (pinfunction "PC14-OSC32_IN(PC14)_3") (pintype "bidirectional+no_connect"))
    )
    (net (code "75") (name "unconnected-(U2A-PC15-OSC32_OUT(PC15)-Pad4)") (class "Default")
      (node (ref "U2") (pin "4") (pinfunction "PC15-OSC32_OUT(PC15)_4") (pintype "bidirectional+no_connect"))
    )
    (net (code "76") (name "unconnected-(U5-A-Pad7)") (class "Default")
      (node (ref "U5") (pin "7") (pinfunction "A_7") (pintype "passive+no_connect"))
    )
    (net (code "77") (name "unconnected-(U5-B-Pad6)") (class "Default")
      (node (ref "U5") (pin "6") (pinfunction "B_6") (pintype "passive+no_connect"))
    )
    (net (code "78") (name "unconnected-(U5-I{slash}PWM-Pad14)") (class "Default")
      (node (ref "U5") (pin "14") (pinfunction "I/PWM_14") (pintype "passive+no_connect"))
    )
    (net (code "79") (name "unconnected-(U5-TEST-Pad5)") (class "Default")
      (node (ref "U5") (pin "5") (pinfunction "TEST_5") (pintype "passive+no_connect"))
    )
    (net (code "80") (name "unconnected-(U5-U-Pad10)") (class "Default")
      (node (ref "U5") (pin "10") (pinfunction "U_10") (pintype "passive+no_connect"))
    )
    (net (code "81") (name "unconnected-(U5-V-Pad9)") (class "Default")
      (node (ref "U5") (pin "9") (pinfunction "V_9") (pintype "passive+no_connect"))
    )
    (net (code "82") (name "unconnected-(U5-W{slash}PWM-Pad8)") (class "Default")
      (node (ref "U5") (pin "8") (pinfunction "W/PWM_8") (pintype "passive+no_connect"))
    )
  )
)
